# design.net
KiCad netlist of a schematic drawn in EAGLE
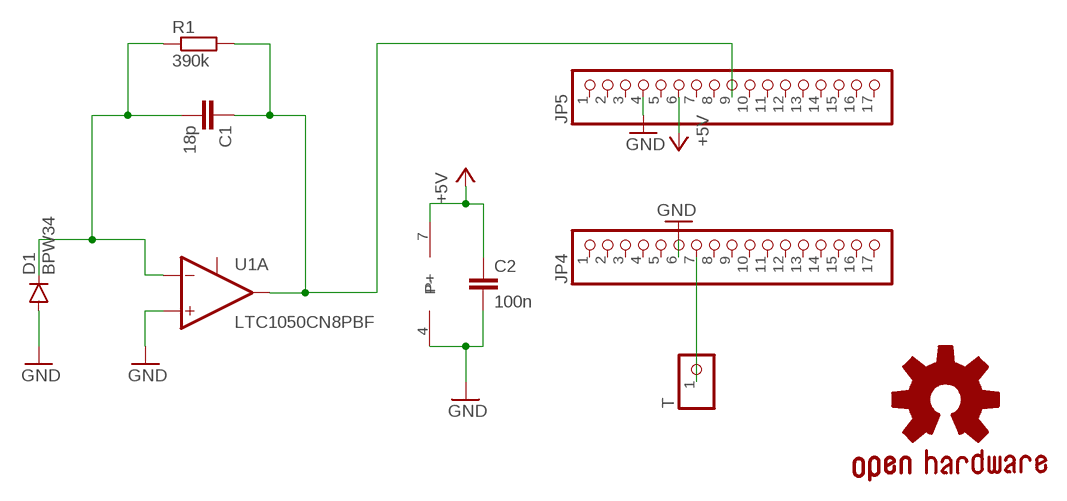
[diagram p0: schematic, sheet 1]

(export (version "E")
  (design (tool "Eeschema 10.0.6"))
  (components
    (comp (ref "C1")
      (value "18p")
      (footprint "eagle-import:C025-025X050")
      (libsource (lib "eagle-import") (part "C-EU025-025X050"))
    )
    (comp (ref "C2")
      (value "100n")
      (footprint "eagle-import:C025-025X050")
      (libsource (lib "eagle-import") (part "C-EU025-025X050"))
    )
    (comp (ref "D1")
      (value "BPW34")
      (footprint "eagle-import:BPW34")
      (libsource (lib "eagle-import") (part "BPW34"))
    )
    (comp (ref "GOLD_ORB_SM1")
      (value "OSHWLOGO_GOLD_ORB_SM")
      (footprint "eagle-import:OSHW2")
      (libsource (lib "eagle-import") (part "OSHWLOGO_GOLD_ORB_SM"))
    )
    (comp (ref "JP4")
      (value "PINHD-1X17")
      (footprint "eagle-import:1X17")
      (libsource (lib "eagle-import") (part "PINHD-1X17"))
    )
    (comp (ref "JP5")
      (value "PINHD-1X17")
      (footprint "eagle-import:1X17")
      (libsource (lib "eagle-import") (part "PINHD-1X17"))
    )
    (comp (ref "R1")
      (value "390k")
      (footprint "eagle-import:0207_2V")
      (libsource (lib "eagle-import") (part "R-EU_0207/2V"))
    )
    (comp (ref "T")
      (value "PINHD-1X1")
      (footprint "eagle-import:1X01")
      (libsource (lib "eagle-import") (part "PINHD-1X1"))
    )
    (comp (ref "U1")
      (value "LTC1050CN8PBF")
      (footprint "eagle-import:DIP254P762X508-8")
      (fields (field (name "MPN") "LTC1050CN8#PBF"))
      (libsource (lib "eagle-import") (part "LTC1050CN8PBF"))
    )
  )
  (nets
    (net (code "1") (name "+5V") (class "Default")
      (node (ref "C2") (pin "1") (pinfunction "1_1") (pintype "passive"))
      (node (ref "JP5") (pin "6") (pinfunction "6_6") (pintype "passive"))
      (node (ref "U1") (pin "7") (pinfunction "P+_7") (pintype "bidirectional"))
    )
    (net (code "2") (name "GND") (class "Default")
      (node (ref "C2") (pin "2") (pinfunction "2_2") (pintype "passive"))
      (node (ref "D1") (pin "P$1") (pinfunction "A_P$1") (pintype "passive"))
      (node (ref "JP4") (pin "6") (pinfunction "6_6") (pintype "passive"))
      (node (ref "JP5") (pin "4") (pinfunction "4_4") (pintype "passive"))
      (node (ref "U1") (pin "3") (pinfunction "IN+_3") (pintype "bidirectional"))
      (node (ref "U1") (pin "4") (pinfunction "P-_4") (pintype "bidirectional"))
    )
    (net (code "3") (name "Net-(D1-C)") (class "Default")
      (node (ref "C1") (pin "2") (pinfunction "2_2") (pintype "passive"))
      (node (ref "D1") (pin "P$2") (pinfunction "C_P$2") (pintype "passive"))
      (node (ref "R1") (pin "1") (pinfunction "1_1") (pintype "passive"))
      (node (ref "U1") (pin "2") (pinfunction "IN-_2") (pintype "bidirectional"))
    )
    (net (code "4") (name "Net-(JP4-Pad7)") (class "Default")
      (node (ref "JP4") (pin "7") (pinfunction "7_7") (pintype "passive"))
      (node (ref "T") (pin "1") (pinfunction "1_1") (pintype "passive"))
    )
    (net (code "5") (name "Net-(U1A-OUT)") (class "Default")
      (node (ref "C1") (pin "1") (pinfunction "1_1") (pintype "passive"))
      (node (ref "JP5") (pin "9") (pinfunction "9_9") (pintype "passive"))
      (node (ref "R1") (pin "2") (pinfunction "2_2") (pintype "passive"))
      (node (ref "U1") (pin "6") (pinfunction "OUT_6") (pintype "bidirectional"))
    )
    (net (code "6") (name "unconnected-(JP4-Pad1)") (class "Default")
      (node (ref "JP4") (pin "1") (pinfunction "1_1") (pintype "passive"))
    )
    (net (code "7") (name "unconnected-(JP4-Pad2)") (class "Default")
      (node (ref "JP4") (pin "2") (pinfunction "2_2") (pintype "passive"))
    )
    (net (code "8") (name "unconnected-(JP4-Pad3)") (class "Default")
      (node (ref "JP4") (pin "3") (pinfunction "3_3") (pintype "passive"))
    )
    (net (code "9") (name "unconnected-(JP4-Pad4)") (class "Default")
      (node (ref "JP4") (pin "4") (pinfunction "4_4") (pintype "passive"))
    )
    (net (code "10") (name "unconnected-(JP4-Pad5)") (class "Default")
      (node (ref "JP4") (pin "5") (pinfunction "5_5") (pintype "passive"))
    )
    (net (code "11") (name "unconnected-(JP4-Pad8)") (class "Default")
      (node (ref "JP4") (pin "8") (pinfunction "8_8") (pintype "passive"))
    )
    (net (code "12") (name "unconnected-(JP4-Pad9)") (class "Default")
      (node (ref "JP4") (pin "9") (pinfunction "9_9") (pintype "passive"))
    )
    (net (code "13") (name "unconnected-(JP4-Pad10)") (class "Default")
      (node (ref "JP4") (pin "10") (pinfunction "10_10") (pintype "passive"))
    )
    (net (code "14") (name "unconnected-(JP4-Pad11)") (class "Default")
      (node (ref "JP4") (pin "11") (pinfunction "11_11") (pintype "passive"))
    )
    (net (code "15") (name "unconnected-(JP4-Pad12)") (class "Default")
      (node (ref "JP4") (pin "12") (pinfunction "12_12") (pintype "passive"))
    )
    (net (code "16") (name "unconnected-(JP4-Pad13)") (class "Default")
      (node (ref "JP4") (pin "13") (pinfunction "13_13") (pintype "passive"))
    )
    (net (code "17") (name "unconnected-(JP4-Pad14)") (class "Default")
      (node (ref "JP4") (pin "14") (pinfunction "14_14") (pintype "passive"))
    )
    (net (code "18") (name "unconnected-(JP4-Pad15)") (class "Default")
      (node (ref "JP4") (pin "15") (pinfunction "15_15") (pintype "passive"))
    )
    (net (code "19") (name "unconnected-(JP4-Pad16)") (class "Default")
      (node (ref "JP4") (pin "16") (pinfunction "16_16") (pintype "passive"))
    )
    (net (code "20") (name "unconnected-(JP4-Pad17)") (class "Default")
      (node (ref "JP4") (pin "17") (pinfunction "17_17") (pintype "passive"))
    )
    (net (code "21") (name "unconnected-(JP5-Pad1)") (class "Default")
      (node (ref "JP5") (pin "1") (pinfunction "1_1") (pintype "passive"))
    )
    (net (code "22") (name "unconnected-(JP5-Pad2)") (class "Default")
      (node (ref "JP5") (pin "2") (pinfunction "2_2") (pintype "passive"))
    )
    (net (code "23") (name "unconnected-(JP5-Pad3)") (class "Default")
      (node (ref "JP5") (pin "3") (pinfunction "3_3") (pintype "passive"))
    )
    (net (code "24") (name "unconnected-(JP5-Pad5)") (class "Default")
      (node (ref "JP5") (pin "5") (pinfunction "5_5") (pintype "passive"))
    )
    (net (code "25") (name "unconnected-(JP5-Pad7)") (class "Default")
      (node (ref "JP5") (pin "7") (pinfunction "7_7") (pintype "passive"))
    )
    (net (code "26") (name "unconnected-(JP5-Pad8)") (class "Default")
      (node (ref "JP5") (pin "8") (pinfunction "8_8") (pintype "passive"))
    )
    (net (code "27") (name "unconnected-(JP5-Pad10)") (class "Default")
      (node (ref "JP5") (pin "10") (pinfunction "10_10") (pintype "passive"))
    )
    (net (code "28") (name "unconnected-(JP5-Pad11)") (class "Default")
      (node (ref "JP5") (pin "11") (pinfunction "11_11") (pintype "passive"))
    )
    (net (code "29") (name "unconnected-(JP5-Pad12)") (class "Default")
      (node (ref "JP5") (pin "12") (pinfunction "12_12") (pintype "passive"))
    )
    (net (code "30") (name "unconnected-(JP5-Pad13)") (class "Default")
      (node (ref "JP5") (pin "13") (pinfunction "13_13") (pintype "passive"))
    )
    (net (code "31") (name "unconnected-(JP5-Pad14)") (class "Default")
      (node (ref "JP5") (pin "14") (pinfunction "14_14") (pintype "passive"))
    )
    (net (code "32") (name "unconnected-(JP5-Pad15)") (class "Default")
      (node (ref "JP5") (pin "15") (pinfunction "15_15") (pintype "passive"))
    )
    (net (code "33") (name "unconnected-(JP5-Pad16)") (class "Default")
      (node (ref "JP5") (pin "16") (pinfunction "16_16") (pintype "passive"))
    )
    (net (code "34") (name "unconnected-(JP5-Pad17)") (class "Default")
      (node (ref "JP5") (pin "17") (pinfunction "17_17") (pintype "passive"))
    )
    (net (code "35") (name "unconnected-(U1A-CLK-Pad5)") (class "Default")
      (node (ref "U1") (pin "5") (pinfunction "CLK_5") (pintype "bidirectional"))
    )
  )
)
